# BusPirate-v3_9-SSOP.net
KiCad netlist of a schematic drawn in EAGLE
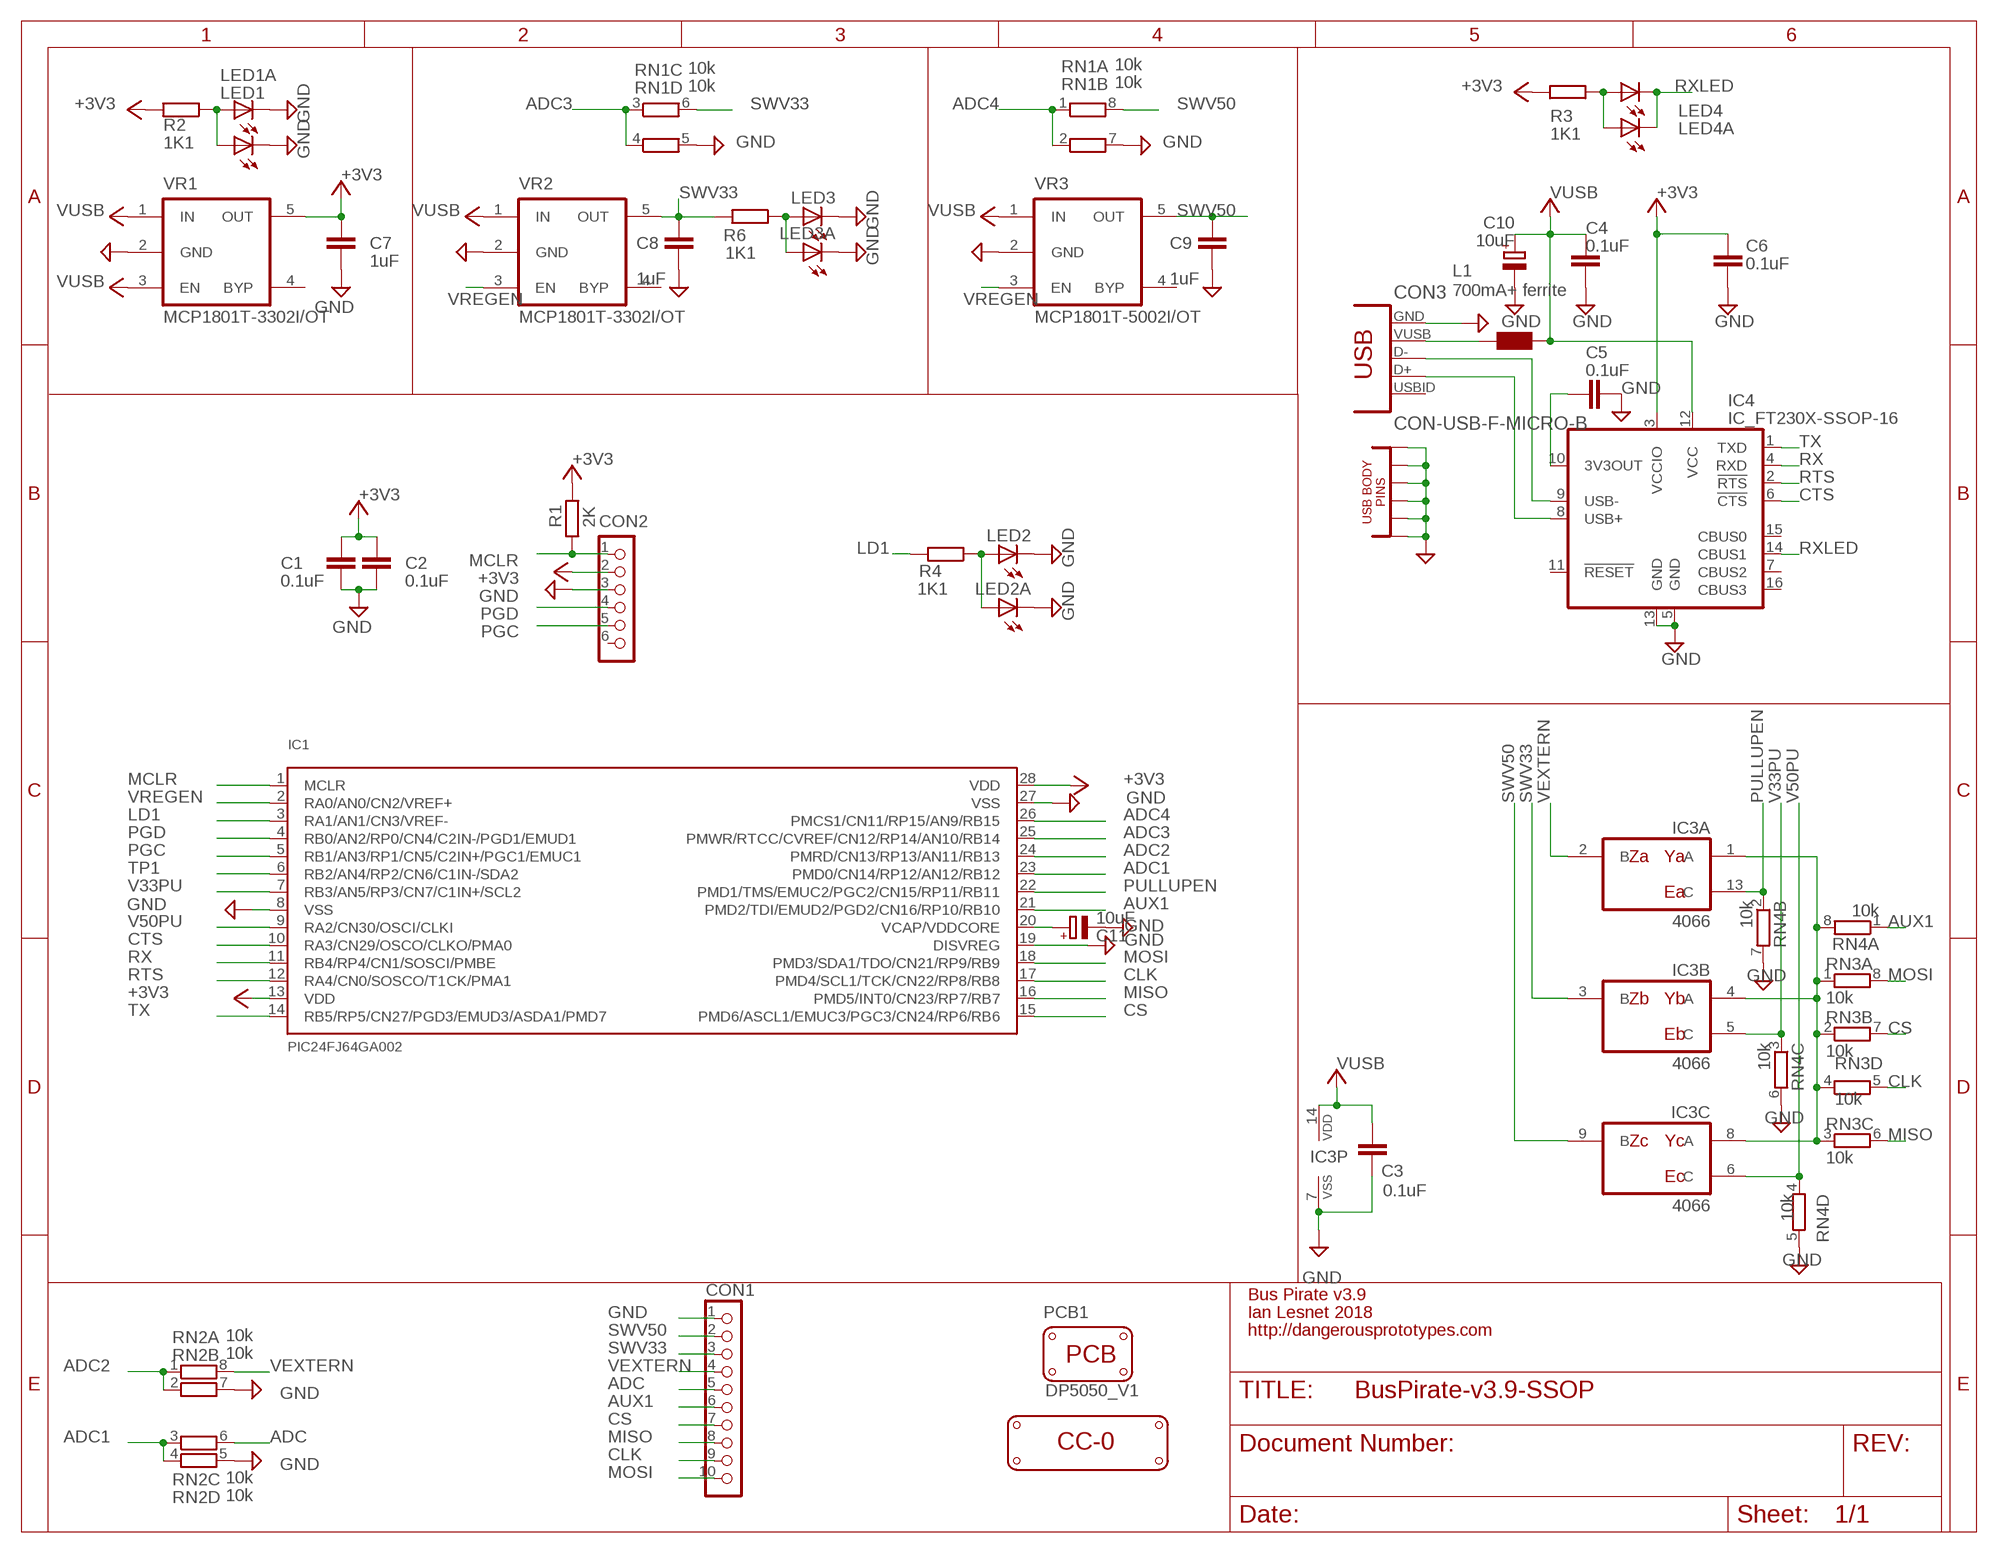
[diagram p0: schematic, sheet 1]

(export (version "E")
  (design (tool "Eeschema 10.0.6"))
  (components
    (comp (ref "C1")
      (value "0.1uF")
      (footprint "eagle-import:C603")
      (libsource (lib "eagle-import") (part "CAPC603"))
    )
    (comp (ref "C2")
      (value "0.1uF")
      (footprint "eagle-import:C603")
      (libsource (lib "eagle-import") (part "CAPC603"))
    )
    (comp (ref "C3")
      (value "0.1uF")
      (footprint "eagle-import:C603")
      (libsource (lib "eagle-import") (part "CAPC603"))
    )
    (comp (ref "C4")
      (value "0.1uF")
      (footprint "eagle-import:C603")
      (libsource (lib "eagle-import") (part "CAPC603"))
    )
    (comp (ref "C5")
      (value "0.1uF")
      (footprint "eagle-import:C603")
      (libsource (lib "eagle-import") (part "CAPC603"))
    )
    (comp (ref "C6")
      (value "0.1uF")
      (footprint "eagle-import:C603")
      (libsource (lib "eagle-import") (part "CAPC603"))
    )
    (comp (ref "C7")
      (value "1uF")
      (footprint "eagle-import:C603")
      (libsource (lib "eagle-import") (part "CAPC603"))
    )
    (comp (ref "C8")
      (value "1uF")
      (footprint "eagle-import:C603")
      (libsource (lib "eagle-import") (part "CAPC603"))
    )
    (comp (ref "C9")
      (value "1uF")
      (footprint "eagle-import:C603")
      (libsource (lib "eagle-import") (part "CAPC603"))
    )
    (comp (ref "C10")
      (value "10uF")
      (footprint "eagle-import:SMC_A")
      (libsource (lib "eagle-import") (part "CPOL-EUSMCA"))
    )
    (comp (ref "C11")
      (value "10uF")
      (footprint "eagle-import:SMC_A")
      (libsource (lib "eagle-import") (part "CPOL-EUSMCA"))
    )
    (comp (ref "CON1")
      (value "CON_HEADER_1X10-RIGHT_ANGLED_PTH_SHROUDED")
      (footprint "eagle-import:M1X10_MALE_RIGHT_ANGLES_PTH_SHROUDED")
      (libsource (lib "eagle-import") (part "CON_HEADER_1X10-RIGHT_ANGLED_PTH_SHROUDED"))
    )
    (comp (ref "CON2")
      (value "CON_HEADER_1X06-PTH")
      (footprint "eagle-import:M1X6")
      (libsource (lib "eagle-import") (part "CON_HEADER_1X06-PTH"))
    )
    (comp (ref "CON3")
      (value "CON-USB-F-MICRO-B")
      (footprint "eagle-import:CON_USB_MICRO-B-1-MD05SMXXX-01")
      (libsource (lib "eagle-import") (part "CON-USB-F-MICRO-B"))
    )
    (comp (ref "IC1")
      (value "PIC24FJ64GA002")
      (footprint "eagle-import:SSOP28")
      (libsource (lib "eagle-import") (part "PIC24FJ64GA002"))
    )
    (comp (ref "IC3")
      (value "4066")
      (footprint "eagle-import:TSSOP14")
      (libsource (lib "eagle-import") (part "4066"))
    )
    (comp (ref "IC4")
      (value "IC_FT230X-SSOP-16")
      (footprint "eagle-import:SSOP-16-FTDI")
      (libsource (lib "eagle-import") (part "IC_FT230X-SSOP-16"))
    )
    (comp (ref "L1")
      (value "700mA+ ferrite")
      (footprint "eagle-import:WE-KI_0805_B")
      (libsource (lib "eagle-import") (part "WE-KIL_0805"))
    )
    (comp (ref "LED1")
      (value "LED-0805")
      (footprint "eagle-import:LED-805")
      (libsource (lib "eagle-import") (part "LED-0805"))
    )
    (comp (ref "LED1A")
      (value "LED-0805")
      (footprint "eagle-import:LED-805")
      (libsource (lib "eagle-import") (part "LED-0805"))
    )
    (comp (ref "LED2")
      (value "LED-0805")
      (footprint "eagle-import:LED-805")
      (libsource (lib "eagle-import") (part "LED-0805"))
    )
    (comp (ref "LED2A")
      (value "LED-0805")
      (footprint "eagle-import:LED-805")
      (libsource (lib "eagle-import") (part "LED-0805"))
    )
    (comp (ref "LED3")
      (value "LED-0805")
      (footprint "eagle-import:LED-805")
      (libsource (lib "eagle-import") (part "LED-0805"))
    )
    (comp (ref "LED3A")
      (value "LED-0805")
      (footprint "eagle-import:LED-805")
      (libsource (lib "eagle-import") (part "LED-0805"))
    )
    (comp (ref "LED4")
      (value "LED-0805")
      (footprint "eagle-import:LED-805")
      (libsource (lib "eagle-import") (part "LED-0805"))
    )
    (comp (ref "LED4A")
      (value "LED-0805")
      (footprint "eagle-import:LED-805")
      (libsource (lib "eagle-import") (part "LED-0805"))
    )
    (comp (ref "LOGO1")
      (value "LOGO_CC-0")
      (footprint "eagle-import:LOGO_CC-0")
      (libsource (lib "eagle-import") (part "LOGO_CC-0"))
    )
    (comp (ref "PCB1")
      (value "PCB_DP_SQUARE-5X5")
      (footprint "eagle-import:DP5050_V1")
      (libsource (lib "eagle-import") (part "PCB_DP_SQUARE-5X5"))
    )
    (comp (ref "R1")
      (value "2K")
      (footprint "eagle-import:R603")
      (libsource (lib "eagle-import") (part "RESISTORR603"))
    )
    (comp (ref "R2")
      (value "1K1")
      (footprint "eagle-import:R603")
      (libsource (lib "eagle-import") (part "RESISTORR603"))
    )
    (comp (ref "R3")
      (value "1K1")
      (footprint "eagle-import:R603")
      (libsource (lib "eagle-import") (part "RESISTORR603"))
    )
    (comp (ref "R4")
      (value "1K1")
      (footprint "eagle-import:R603")
      (libsource (lib "eagle-import") (part "RESISTORR603"))
    )
    (comp (ref "R6")
      (value "1K1")
      (footprint "eagle-import:R603")
      (libsource (lib "eagle-import") (part "RESISTORR603"))
    )
    (comp (ref "RN1")
      (value "10k")
      (footprint "eagle-import:RN8P-4R-CRA06S")
      (libsource (lib "eagle-import") (part "RNETWORK"))
    )
    (comp (ref "RN2")
      (value "10k")
      (footprint "eagle-import:RN8P-4R-CRA06S")
      (libsource (lib "eagle-import") (part "RNETWORK"))
    )
    (comp (ref "RN3")
      (value "10k")
      (footprint "eagle-import:RN8P-4R-CRA06S")
      (libsource (lib "eagle-import") (part "RNETWORK"))
    )
    (comp (ref "RN4")
      (value "10k")
      (footprint "eagle-import:RN8P-4R-CRA06S")
      (libsource (lib "eagle-import") (part "RNETWORK"))
    )
    (comp (ref "VR1")
      (value "MCP1801T-3302I/OT")
      (footprint "eagle-import:SOT-23-5")
      (libsource (lib "eagle-import") (part "MIC5205"))
    )
    (comp (ref "VR2")
      (value "MCP1801T-3302I/OT")
      (footprint "eagle-import:SOT-23-5")
      (libsource (lib "eagle-import") (part "MIC5205"))
    )
    (comp (ref "VR3")
      (value "MCP1801T-5002I/OT")
      (footprint "eagle-import:SOT-23-5")
      (libsource (lib "eagle-import") (part "MIC5205"))
    )
  )
  (nets
    (net (code "1") (name "/ADC") (class "Default")
      (node (ref "CON1") (pin "5") (pinfunction "5_5") (pintype "passive"))
      (node (ref "RN2") (pin "6") (pinfunction "2_6") (pintype "passive"))
    )
    (net (code "2") (name "/ADC1") (class "Default")
      (node (ref "IC1") (pin "23") (pinfunction "PMD0/CN14/RP12/AN12/RB12_23") (pintype "bidirectional"))
      (node (ref "RN2") (pin "3") (pinfunction "1_3") (pintype "passive"))
      (node (ref "RN2") (pin "4") (pinfunction "1_4") (pintype "passive"))
    )
    (net (code "3") (name "/ADC2") (class "Default")
      (node (ref "IC1") (pin "24") (pinfunction "PMRD/CN13/RP13/AN11/RB13_24") (pintype "bidirectional"))
      (node (ref "RN2") (pin "1") (pinfunction "1_1") (pintype "passive"))
      (node (ref "RN2") (pin "2") (pinfunction "1_2") (pintype "passive"))
    )
    (net (code "4") (name "/ADC3") (class "Default")
      (node (ref "IC1") (pin "25") (pinfunction "PMWR/RTCC/CVREF/CN12/RP14/AN10/RB14_25") (pintype "bidirectional"))
      (node (ref "RN1") (pin "3") (pinfunction "1_3") (pintype "passive"))
      (node (ref "RN1") (pin "4") (pinfunction "1_4") (pintype "passive"))
    )
    (net (code "5") (name "/ADC4") (class "Default")
      (node (ref "IC1") (pin "26") (pinfunction "PMCS1/CN11/RP15/AN9/RB15_26") (pintype "bidirectional"))
      (node (ref "RN1") (pin "1") (pinfunction "1_1") (pintype "passive"))
      (node (ref "RN1") (pin "2") (pinfunction "1_2") (pintype "passive"))
    )
    (net (code "6") (name "/AUX1") (class "Default")
      (node (ref "CON1") (pin "6") (pinfunction "6_6") (pintype "passive"))
      (node (ref "IC1") (pin "21") (pinfunction "PMD2/TDI/EMUD2/PGD2/CN16/RP10/RB10_21") (pintype "bidirectional"))
      (node (ref "RN4") (pin "1") (pinfunction "1_1") (pintype "passive"))
    )
    (net (code "7") (name "/CLK") (class "Default")
      (node (ref "CON1") (pin "9") (pinfunction "9_9") (pintype "passive"))
      (node (ref "IC1") (pin "17") (pinfunction "PMD4/SCL1/TCK/CN22/RP8/RB8_17") (pintype "bidirectional"))
      (node (ref "RN3") (pin "5") (pinfunction "2_5") (pintype "passive"))
    )
    (net (code "8") (name "/CS") (class "Default")
      (node (ref "CON1") (pin "7") (pinfunction "7_7") (pintype "passive"))
      (node (ref "IC1") (pin "15") (pinfunction "PMD6/ASCL1/EMUC3/PGC3/CN24/RP6/RB6_15") (pintype "bidirectional"))
      (node (ref "RN3") (pin "7") (pinfunction "2_7") (pintype "passive"))
    )
    (net (code "9") (name "/CTS") (class "Default")
      (node (ref "IC1") (pin "10") (pinfunction "RA3/CN29/OSCO/CLKO/PMA0_10") (pintype "bidirectional"))
      (node (ref "IC4") (pin "6") (pinfunction "~{CTS}_6") (pintype "bidirectional"))
    )
    (net (code "10") (name "/LD1") (class "Default")
      (node (ref "IC1") (pin "3") (pinfunction "RA1/AN1/CN3/VREF-_3") (pintype "bidirectional"))
      (node (ref "R4") (pin "2") (pinfunction "2_2") (pintype "passive"))
    )
    (net (code "11") (name "/MCLR") (class "Default")
      (node (ref "CON2") (pin "1") (pinfunction "1_1") (pintype "bidirectional"))
      (node (ref "IC1") (pin "1") (pinfunction "MCLR_1") (pintype "input"))
      (node (ref "R1") (pin "1") (pinfunction "1_1") (pintype "passive"))
    )
    (net (code "12") (name "/MISO") (class "Default")
      (node (ref "CON1") (pin "8") (pinfunction "8_8") (pintype "passive"))
      (node (ref "IC1") (pin "16") (pinfunction "PMD5/INT0/CN23/RP7/RB7_16") (pintype "bidirectional"))
      (node (ref "RN3") (pin "6") (pinfunction "2_6") (pintype "passive"))
    )
    (net (code "13") (name "/MOSI") (class "Default")
      (node (ref "CON1") (pin "10") (pinfunction "10_10") (pintype "passive"))
      (node (ref "IC1") (pin "18") (pinfunction "PMD3/SDA1/TDO/CN21/RP9/RB9_18") (pintype "bidirectional"))
      (node (ref "RN3") (pin "8") (pinfunction "2_8") (pintype "passive"))
    )
    (net (code "14") (name "/PGC") (class "Default")
      (node (ref "CON2") (pin "5") (pinfunction "5_5") (pintype "passive"))
      (node (ref "IC1") (pin "5") (pinfunction "RB1/AN3/RP1/CN5/C2IN+/PGC1/EMUC1_5") (pintype "bidirectional"))
    )
    (net (code "15") (name "/PGD") (class "Default")
      (node (ref "CON2") (pin "4") (pinfunction "4_4") (pintype "passive"))
      (node (ref "IC1") (pin "4") (pinfunction "RB0/AN2/RP0/CN4/C2IN-/PGD1/EMUD1_4") (pintype "bidirectional"))
    )
    (net (code "16") (name "/PULLUPEN") (class "Default")
      (node (ref "IC1") (pin "22") (pinfunction "PMD1/TMS/EMUC2/PGC2/CN15/RP11/RB11_22") (pintype "bidirectional"))
      (node (ref "IC3") (pin "13") (pinfunction "C_13") (pintype "input"))
      (node (ref "RN4") (pin "2") (pinfunction "1_2") (pintype "passive"))
    )
    (net (code "17") (name "/RTS") (class "Default")
      (node (ref "IC1") (pin "12") (pinfunction "RA4/CN0/SOSCO/T1CK/PMA1_12") (pintype "bidirectional"))
      (node (ref "IC4") (pin "2") (pinfunction "~{RTS}_2") (pintype "bidirectional"))
    )
    (net (code "18") (name "/RX") (class "Default")
      (node (ref "IC1") (pin "11") (pinfunction "RB4/RP4/CN1/SOSCI/PMBE_11") (pintype "bidirectional"))
      (node (ref "IC4") (pin "4") (pinfunction "RXD_4") (pintype "input"))
    )
    (net (code "19") (name "/RXLED") (class "Default")
      (node (ref "IC4") (pin "14") (pinfunction "CBUS1_14") (pintype "bidirectional"))
      (node (ref "LED4") (pin "C") (pinfunction "C_C") (pintype "passive"))
      (node (ref "LED4A") (pin "C") (pinfunction "C_C") (pintype "passive"))
    )
    (net (code "20") (name "/SWV33") (class "Default")
      (node (ref "C8") (pin "1") (pinfunction "1_1") (pintype "passive"))
      (node (ref "CON1") (pin "3") (pinfunction "3_3") (pintype "passive"))
      (node (ref "IC3") (pin "3") (pinfunction "B_3") (pintype "tri_state"))
      (node (ref "R6") (pin "2") (pinfunction "2_2") (pintype "passive"))
      (node (ref "RN1") (pin "6") (pinfunction "2_6") (pintype "passive"))
      (node (ref "VR2") (pin "5") (pinfunction "OUT_5") (pintype "bidirectional"))
    )
    (net (code "21") (name "/SWV50") (class "Default")
      (node (ref "C9") (pin "1") (pinfunction "1_1") (pintype "passive"))
      (node (ref "CON1") (pin "2") (pinfunction "2_2") (pintype "passive"))
      (node (ref "IC3") (pin "9") (pinfunction "B_9") (pintype "tri_state"))
      (node (ref "RN1") (pin "8") (pinfunction "2_8") (pintype "passive"))
      (node (ref "VR3") (pin "5") (pinfunction "OUT_5") (pintype "bidirectional"))
    )
    (net (code "22") (name "/TP1") (class "Default")
      (node (ref "IC1") (pin "6") (pinfunction "RB2/AN4/RP2/CN6/C1IN-/SDA2_6") (pintype "bidirectional"))
    )
    (net (code "23") (name "/TX") (class "Default")
      (node (ref "IC1") (pin "14") (pinfunction "RB5/RP5/CN27/PGD3/EMUD3/ASDA1/PMD7_14") (pintype "bidirectional"))
      (node (ref "IC4") (pin "1") (pinfunction "TXD_1") (pintype "output"))
    )
    (net (code "24") (name "/V33PU") (class "Default")
      (node (ref "IC1") (pin "7") (pinfunction "RB3/AN5/RP3/CN7/C1IN+/SCL2_7") (pintype "bidirectional"))
      (node (ref "IC3") (pin "5") (pinfunction "C_5") (pintype "input"))
      (node (ref "RN4") (pin "3") (pinfunction "1_3") (pintype "passive"))
    )
    (net (code "25") (name "/V50PU") (class "Default")
      (node (ref "IC1") (pin "9") (pinfunction "RA2/CN30/OSCI/CLKI_9") (pintype "bidirectional"))
      (node (ref "IC3") (pin "6") (pinfunction "C_6") (pintype "input"))
      (node (ref "RN4") (pin "4") (pinfunction "1_4") (pintype "passive"))
    )
    (net (code "26") (name "/VEXTERN") (class "Default")
      (node (ref "CON1") (pin "4") (pinfunction "4_4") (pintype "passive"))
      (node (ref "IC3") (pin "2") (pinfunction "B_2") (pintype "tri_state"))
      (node (ref "RN2") (pin "8") (pinfunction "2_8") (pintype "passive"))
    )
    (net (code "27") (name "/VREGEN") (class "Default")
      (node (ref "IC1") (pin "2") (pinfunction "RA0/AN0/CN2/VREF+_2") (pintype "bidirectional"))
      (node (ref "VR2") (pin "3") (pinfunction "EN_3") (pintype "bidirectional"))
      (node (ref "VR3") (pin "3") (pinfunction "EN_3") (pintype "bidirectional"))
    )
    (net (code "28") (name "GND") (class "Default")
      (node (ref "C1") (pin "2") (pinfunction "2_2") (pintype "passive"))
      (node (ref "C10") (pin "-") (pinfunction "-_-") (pintype "passive"))
      (node (ref "C11") (pin "-") (pinfunction "-_-") (pintype "passive"))
      (node (ref "C2") (pin "2") (pinfunction "2_2") (pintype "passive"))
      (node (ref "C3") (pin "2") (pinfunction "2_2") (pintype "passive"))
      (node (ref "C4") (pin "2") (pinfunction "2_2") (pintype "passive"))
      (node (ref "C5") (pin "2") (pinfunction "2_2") (pintype "passive"))
      (node (ref "C6") (pin "2") (pinfunction "2_2") (pintype "passive"))
      (node (ref "C7") (pin "2") (pinfunction "2_2") (pintype "passive"))
      (node (ref "C8") (pin "2") (pinfunction "2_2") (pintype "passive"))
      (node (ref "C9") (pin "2") (pinfunction "2_2") (pintype "passive"))
      (node (ref "CON1") (pin "1") (pinfunction "1_1") (pintype "passive"))
      (node (ref "CON2") (pin "3") (pinfunction "3_3") (pintype "passive"))
      (node (ref "CON3") (pin "GND1") (pinfunction "P$1_GND1") (pintype "passive"))
      (node (ref "CON3") (pin "GND2") (pinfunction "P$2_GND2") (pintype "passive"))
      (node (ref "CON3") (pin "GND3") (pinfunction "P$3_GND3") (pintype "passive"))
      (node (ref "CON3") (pin "GND4") (pinfunction "P$4_GND4") (pintype "passive"))
      (node (ref "CON3") (pin "GND5") (pinfunction "P$5_GND5") (pintype "passive"))
      (node (ref "CON3") (pin "GND6") (pinfunction "P$6_GND6") (pintype "passive"))
      (node (ref "CON3") (pin "P5") (pinfunction "GND_P5") (pintype "bidirectional"))
      (node (ref "IC1") (pin "19") (pinfunction "DISVREG_19") (pintype "power_in"))
      (node (ref "IC1") (pin "27") (pinfunction "VSS_27") (pintype "power_in"))
      (node (ref "IC1") (pin "8") (pinfunction "VSS_8") (pintype "power_in"))
      (node (ref "IC3") (pin "7") (pinfunction "VSS_7") (pintype "power_in"))
      (node (ref "IC4") (pin "13") (pinfunction "GND_13") (pintype "power_in"))
      (node (ref "IC4") (pin "5") (pinfunction "GND_5") (pintype "power_in"))
      (node (ref "LED1") (pin "C") (pinfunction "C_C") (pintype "passive"))
      (node (ref "LED1A") (pin "C") (pinfunction "C_C") (pintype "passive"))
      (node (ref "LED2") (pin "C") (pinfunction "C_C") (pintype "passive"))
      (node (ref "LED2A") (pin "C") (pinfunction "C_C") (pintype "passive"))
      (node (ref "LED3") (pin "C") (pinfunction "C_C") (pintype "passive"))
      (node (ref "LED3A") (pin "C") (pinfunction "C_C") (pintype "passive"))
      (node (ref "RN1") (pin "5") (pinfunction "2_5") (pintype "passive"))
      (node (ref "RN1") (pin "7") (pinfunction "2_7") (pintype "passive"))
      (node (ref "RN2") (pin "5") (pinfunction "2_5") (pintype "passive"))
      (node (ref "RN2") (pin "7") (pinfunction "2_7") (pintype "passive"))
      (node (ref "RN4") (pin "5") (pinfunction "2_5") (pintype "passive"))
      (node (ref "RN4") (pin "6") (pinfunction "2_6") (pintype "passive"))
      (node (ref "RN4") (pin "7") (pinfunction "2_7") (pintype "passive"))
      (node (ref "VR1") (pin "2") (pinfunction "GND_2") (pintype "bidirectional"))
      (node (ref "VR2") (pin "2") (pinfunction "GND_2") (pintype "bidirectional"))
      (node (ref "VR3") (pin "2") (pinfunction "GND_2") (pintype "bidirectional"))
    )
    (net (code "29") (name "Net-(CON3A-D+)") (class "Default")
      (node (ref "CON3") (pin "P3") (pinfunction "D+_P3") (pintype "bidirectional"))
      (node (ref "IC4") (pin "8") (pinfunction "USB+_8") (pintype "output"))
    )
    (net (code "30") (name "Net-(CON3A-D-)") (class "Default")
      (node (ref "CON3") (pin "P2") (pinfunction "D-_P2") (pintype "bidirectional"))
      (node (ref "IC4") (pin "9") (pinfunction "USB-_9") (pintype "input"))
    )
    (net (code "31") (name "Net-(CON3A-VUSB)") (class "Default")
      (node (ref "CON3") (pin "P1") (pinfunction "VUSB_P1") (pintype "bidirectional"))
      (node (ref "L1") (pin "2") (pinfunction "1_2") (pintype "passive"))
    )
    (net (code "32") (name "Net-(IC1-VCAP{slash}VDDCORE)") (class "Default")
      (node (ref "C11") (pin "+") (pinfunction "+_+") (pintype "passive"))
      (node (ref "IC1") (pin "20") (pinfunction "VCAP/VDDCORE_20") (pintype "power_in"))
    )
    (net (code "33") (name "Net-(IC3A-A)") (class "Default")
      (node (ref "IC3") (pin "1") (pinfunction "A_1") (pintype "tri_state"))
      (node (ref "IC3") (pin "4") (pinfunction "A_4") (pintype "tri_state"))
      (node (ref "IC3") (pin "8") (pinfunction "A_8") (pintype "tri_state"))
      (node (ref "RN3") (pin "1") (pinfunction "1_1") (pintype "passive"))
      (node (ref "RN3") (pin "2") (pinfunction "1_2") (pintype "passive"))
      (node (ref "RN3") (pin "3") (pinfunction "1_3") (pintype "passive"))
      (node (ref "RN3") (pin "4") (pinfunction "1_4") (pintype "passive"))
      (node (ref "RN4") (pin "8") (pinfunction "2_8") (pintype "passive"))
    )
    (net (code "34") (name "Net-(IC4-3V3OUT)") (class "Default")
      (node (ref "C5") (pin "1") (pinfunction "1_1") (pintype "passive"))
      (node (ref "IC4") (pin "10") (pinfunction "3V3OUT_10") (pintype "power_in"))
    )
    (net (code "35") (name "Net-(LED1-PadA)") (class "Default")
      (node (ref "LED1") (pin "A") (pinfunction "A_A") (pintype "passive"))
      (node (ref "LED1A") (pin "A") (pinfunction "A_A") (pintype "passive"))
      (node (ref "R2") (pin "1") (pinfunction "1_1") (pintype "passive"))
    )
    (net (code "36") (name "Net-(LED2-PadA)") (class "Default")
      (node (ref "LED2") (pin "A") (pinfunction "A_A") (pintype "passive"))
      (node (ref "LED2A") (pin "A") (pinfunction "A_A") (pintype "passive"))
      (node (ref "R4") (pin "1") (pinfunction "1_1") (pintype "passive"))
    )
    (net (code "37") (name "Net-(LED3-PadA)") (class "Default")
      (node (ref "LED3") (pin "A") (pinfunction "A_A") (pintype "passive"))
      (node (ref "LED3A") (pin "A") (pinfunction "A_A") (pintype "passive"))
      (node (ref "R6") (pin "1") (pinfunction "1_1") (pintype "passive"))
    )
    (net (code "38") (name "Net-(LED4-PadA)") (class "Default")
      (node (ref "LED4") (pin "A") (pinfunction "A_A") (pintype "passive"))
      (node (ref "LED4A") (pin "A") (pinfunction "A_A") (pintype "passive"))
      (node (ref "R3") (pin "1") (pinfunction "1_1") (pintype "passive"))
    )
    (net (code "39") (name "SUPPLY_+3V3") (class "Default")
      (node (ref "C1") (pin "1") (pinfunction "1_1") (pintype "passive"))
      (node (ref "C2") (pin "1") (pinfunction "1_1") (pintype "passive"))
      (node (ref "C6") (pin "1") (pinfunction "1_1") (pintype "passive"))
      (node (ref "C7") (pin "1") (pinfunction "1_1") (pintype "passive"))
      (node (ref "CON2") (pin "2") (pinfunction "2_2") (pintype "bidirectional"))
      (node (ref "IC1") (pin "13") (pinfunction "VDD_13") (pintype "power_in"))
      (node (ref "IC1") (pin "28") (pinfunction "VDD_28") (pintype "power_in"))
      (node (ref "IC4") (pin "3") (pinfunction "VCCIO_3") (pintype "power_in"))
      (node (ref "R1") (pin "2") (pinfunction "2_2") (pintype "passive"))
      (node (ref "R2") (pin "2") (pinfunction "2_2") (pintype "passive"))
      (node (ref "R3") (pin "2") (pinfunction "2_2") (pintype "passive"))
      (node (ref "VR1") (pin "5") (pinfunction "OUT_5") (pintype "bidirectional"))
    )
    (net (code "40") (name "SUPPLY_VUSB") (class "Default")
      (node (ref "C10") (pin "+") (pinfunction "+_+") (pintype "passive"))
      (node (ref "C3") (pin "1") (pinfunction "1_1") (pintype "passive"))
      (node (ref "C4") (pin "1") (pinfunction "1_1") (pintype "passive"))
      (node (ref "IC3") (pin "14") (pinfunction "VDD_14") (pintype "power_in"))
      (node (ref "IC4") (pin "12") (pinfunction "VCC_12") (pintype "power_in"))
      (node (ref "L1") (pin "1") (pinfunction "2_1") (pintype "passive"))
      (node (ref "VR1") (pin "1") (pinfunction "IN_1") (pintype "bidirectional"))
      (node (ref "VR1") (pin "3") (pinfunction "EN_3") (pintype "bidirectional"))
      (node (ref "VR2") (pin "1") (pinfunction "IN_1") (pintype "bidirectional"))
      (node (ref "VR3") (pin "1") (pinfunction "IN_1") (pintype "bidirectional"))
    )
    (net (code "41") (name "unconnected-(CON2-Pad6)") (class "Default")
      (node (ref "CON2") (pin "6") (pinfunction "6_6") (pintype "passive"))
    )
    (net (code "42") (name "unconnected-(CON3A-USBID-PadP4)") (class "Default")
      (node (ref "CON3") (pin "P4") (pinfunction "USBID_P4") (pintype "bidirectional"))
    )
    (net (code "43") (name "unconnected-(IC4-CBUS0-Pad15)") (class "Default")
      (node (ref "IC4") (pin "15") (pinfunction "CBUS0_15") (pintype "bidirectional"))
    )
    (net (code "44") (name "unconnected-(IC4-CBUS2-Pad7)") (class "Default")
      (node (ref "IC4") (pin "7") (pinfunction "CBUS2_7") (pintype "bidirectional"))
    )
    (net (code "45") (name "unconnected-(IC4-CBUS3-Pad16)") (class "Default")
      (node (ref "IC4") (pin "16") (pinfunction "CBUS3_16") (pintype "bidirectional"))
    )
    (net (code "46") (name "unconnected-(IC4-~{RESET}-Pad11)") (class "Default")
      (node (ref "IC4") (pin "11") (pinfunction "~{RESET}_11") (pintype "bidirectional"))
    )
    (net (code "47") (name "unconnected-(VR1-BYP-Pad4)") (class "Default")
      (node (ref "VR1") (pin "4") (pinfunction "BYP_4") (pintype "bidirectional"))
    )
    (net (code "48") (name "unconnected-(VR2-BYP-Pad4)") (class "Default")
      (node (ref "VR2") (pin "4") (pinfunction "BYP_4") (pintype "bidirectional"))
    )
    (net (code "49") (name "unconnected-(VR3-BYP-Pad4)") (class "Default")
      (node (ref "VR3") (pin "4") (pinfunction "BYP_4") (pintype "bidirectional"))
    )
  )
)
